# dataloggerver2_0.net
KiCad netlist of a schematic drawn in EAGLE
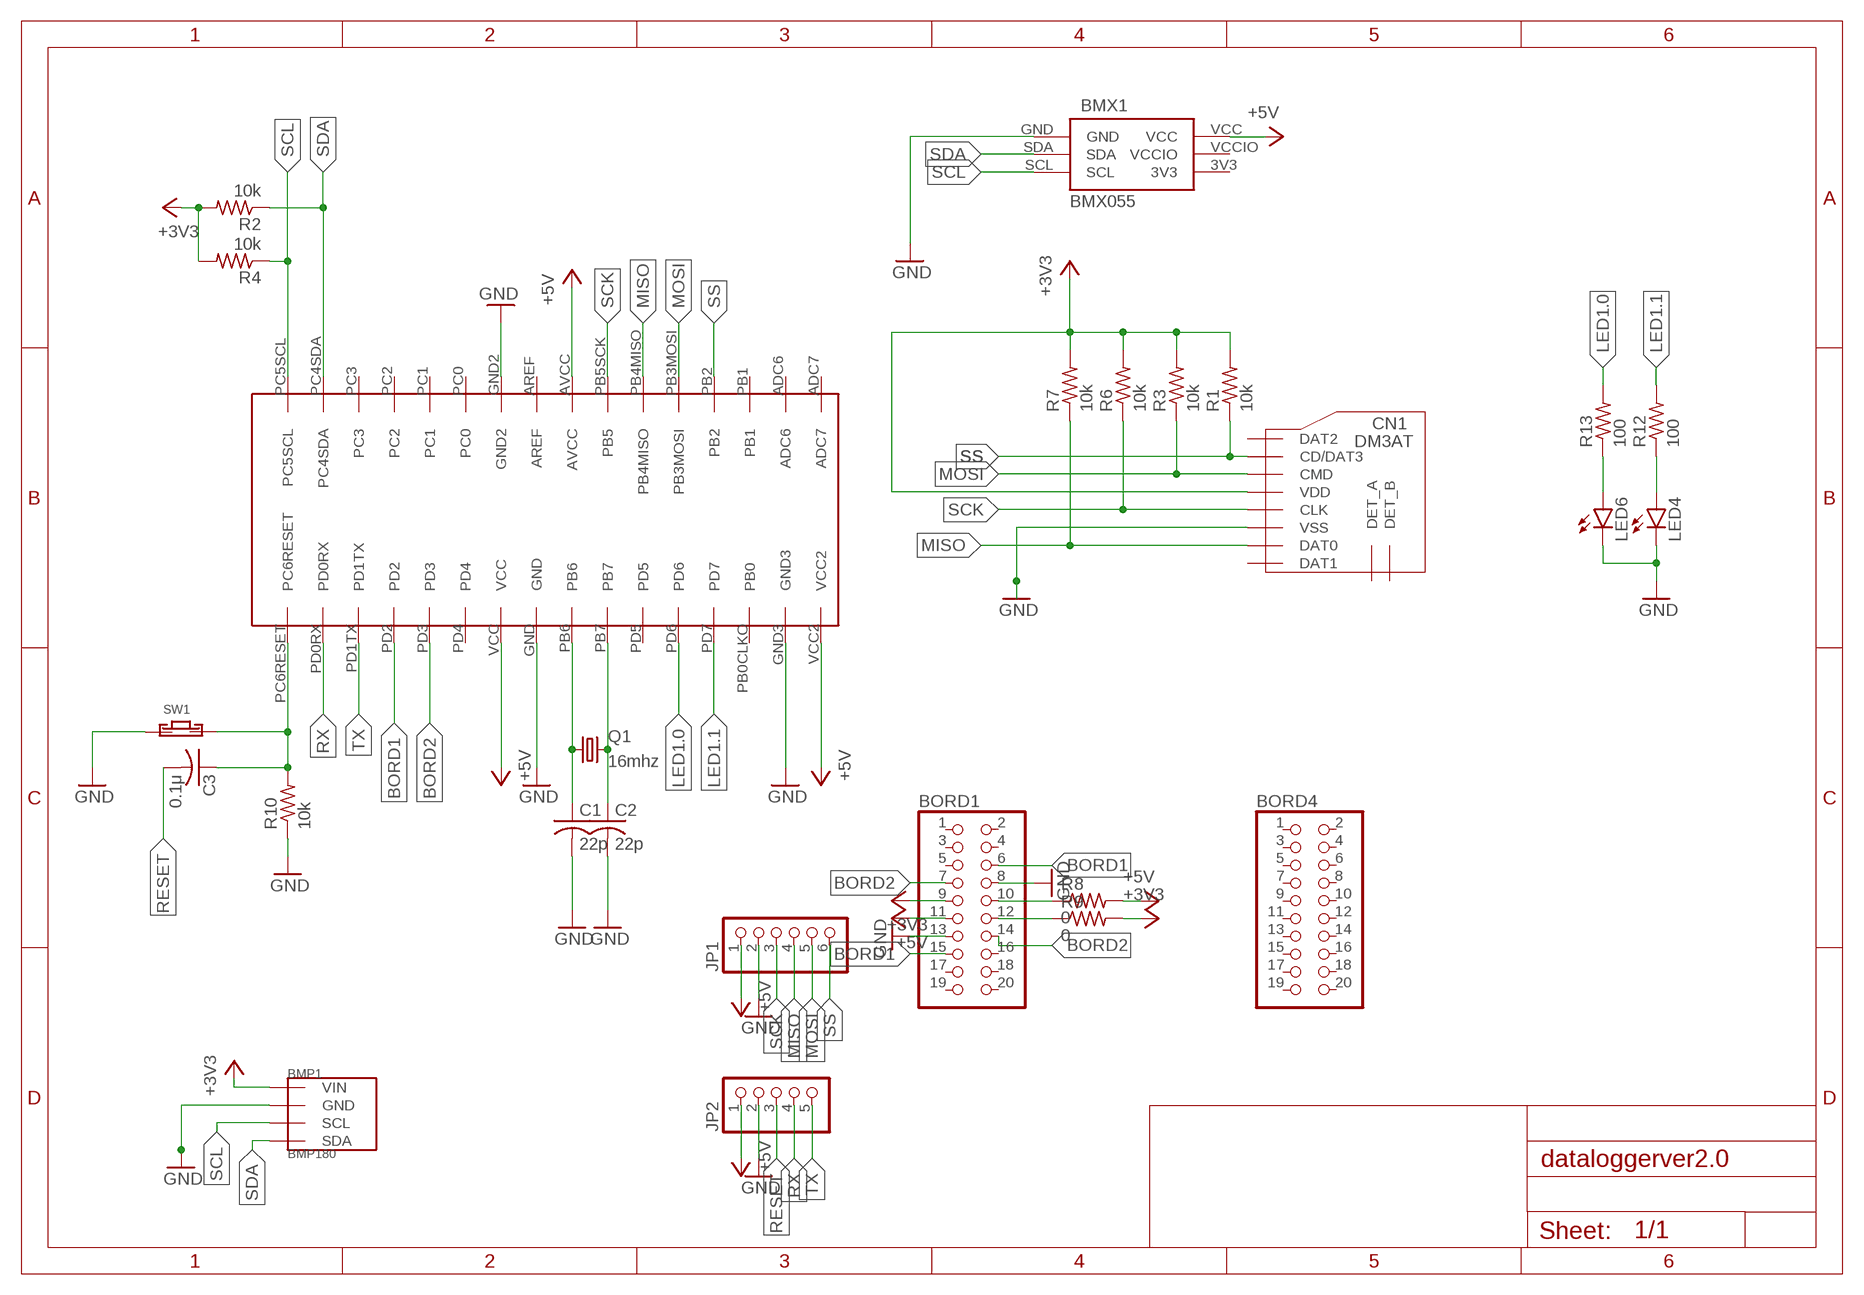
[diagram p0: schematic, sheet 1]

(export (version "E")
  (design (tool "Eeschema 10.0.6"))
  (components
    (comp (ref "BMP1")
      (value "BMP180")
      (footprint "eagle-import:GY-68")
      (libsource (lib "eagle-import") (part "BMP180"))
    )
    (comp (ref "BMX1")
      (value "BMX055")
      (footprint "eagle-import:BMX055")
      (libsource (lib "eagle-import") (part "BMX055"))
    )
    (comp (ref "BORD1")
      (value "PINHD-2X10/90")
      (footprint "eagle-import:2X10_90")
      (libsource (lib "eagle-import") (part "PINHD-2X10/90"))
    )
    (comp (ref "BORD4")
      (value "PINHD-2X10/90")
      (footprint "eagle-import:2X10_90")
      (libsource (lib "eagle-import") (part "PINHD-2X10/90"))
    )
    (comp (ref "C1")
      (value "22p")
      (footprint "eagle-import:C1608")
      (libsource (lib "eagle-import") (part "C-USC1608"))
    )
    (comp (ref "C2")
      (value "22p")
      (footprint "eagle-import:C1608")
      (libsource (lib "eagle-import") (part "C-USC1608"))
    )
    (comp (ref "C3")
      (value "0.1μ")
      (footprint "eagle-import:C1608")
      (libsource (lib "eagle-import") (part "C-USC1608"))
    )
    (comp (ref "CN1")
      (value "DM3AT")
      (footprint "eagle-import:DM3AT")
      (libsource (lib "eagle-import") (part "DM3AT"))
    )
    (comp (ref "JP1")
      (value "PINHD-1X6")
      (footprint "eagle-import:1X06")
      (libsource (lib "eagle-import") (part "PINHD-1X6"))
    )
    (comp (ref "JP2")
      (value "PINHD-1X5")
      (footprint "eagle-import:1X05")
      (libsource (lib "eagle-import") (part "PINHD-1X5"))
    )
    (comp (ref "LED4")
      (value "LED5MM")
      (footprint "eagle-import:LED5MM")
      (libsource (lib "eagle-import") (part "LED5MM"))
    )
    (comp (ref "LED6")
      (value "LED5MM")
      (footprint "eagle-import:LED5MM")
      (libsource (lib "eagle-import") (part "LED5MM"))
    )
    (comp (ref "Q1")
      (value "16mhz")
      (footprint "eagle-import:HC49UP")
      (libsource (lib "eagle-import") (part "CRYSTALHC49UP"))
    )
    (comp (ref "R1")
      (value "10k")
      (footprint "eagle-import:R0603")
      (libsource (lib "eagle-import") (part "R-US_R0603"))
    )
    (comp (ref "R2")
      (value "10k")
      (footprint "eagle-import:R0603")
      (libsource (lib "eagle-import") (part "R-US_R0603"))
    )
    (comp (ref "R3")
      (value "10k")
      (footprint "eagle-import:R0603")
      (libsource (lib "eagle-import") (part "R-US_R0603"))
    )
    (comp (ref "R4")
      (value "10k")
      (footprint "eagle-import:R0603")
      (libsource (lib "eagle-import") (part "R-US_R0603"))
    )
    (comp (ref "R6")
      (value "10k")
      (footprint "eagle-import:R0603")
      (libsource (lib "eagle-import") (part "R-US_R0603"))
    )
    (comp (ref "R7")
      (value "10k")
      (footprint "eagle-import:R0603")
      (libsource (lib "eagle-import") (part "R-US_R0603"))
    )
    (comp (ref "R8")
      (value "0")
      (footprint "eagle-import:R0603")
      (libsource (lib "eagle-import") (part "R-US_R0603"))
    )
    (comp (ref "R9")
      (value "0")
      (footprint "eagle-import:R0603")
      (libsource (lib "eagle-import") (part "R-US_R0603"))
    )
    (comp (ref "R10")
      (value "10k")
      (footprint "eagle-import:R0603")
      (libsource (lib "eagle-import") (part "R-US_R0603"))
    )
    (comp (ref "R12")
      (value "100")
      (footprint "eagle-import:R0603")
      (libsource (lib "eagle-import") (part "R-US_R0603"))
    )
    (comp (ref "R13")
      (value "100")
      (footprint "eagle-import:R0603")
      (libsource (lib "eagle-import") (part "R-US_R0603"))
    )
    (comp (ref "SW1")
      (value "TVAF06-A020B-R")
      (footprint "eagle-import:TVAF06-A020B-R")
      (libsource (lib "eagle-import") (part "TVAF06-A020B-R"))
    )
    (comp (ref "U$1")
      (value "ATMEGA328P-AU")
      (footprint "eagle-import:ATMEGA328P-AU")
      (libsource (lib "eagle-import") (part "ATMEGA328P-AU"))
    )
  )
  (nets
    (net (code "1") (name "+3V3") (class "Default")
      (node (ref "BMP1") (pin "P1") (pinfunction "VIN_P1") (pintype "bidirectional"))
      (node (ref "BORD1") (pin "9") (pinfunction "9_9") (pintype "passive"))
      (node (ref "CN1") (pin "VDD") (pinfunction "VDD_VDD") (pintype "bidirectional"))
      (node (ref "R1") (pin "2") (pinfunction "2_2") (pintype "passive"))
      (node (ref "R2") (pin "2") (pinfunction "2_2") (pintype "passive"))
      (node (ref "R3") (pin "2") (pinfunction "2_2") (pintype "passive"))
      (node (ref "R4") (pin "2") (pinfunction "2_2") (pintype "passive"))
      (node (ref "R6") (pin "2") (pinfunction "2_2") (pintype "passive"))
      (node (ref "R7") (pin "2") (pinfunction "2_2") (pintype "passive"))
      (node (ref "R9") (pin "2") (pinfunction "2_2") (pintype "passive"))
    )
    (net (code "2") (name "+5V") (class "Default")
      (node (ref "BMX1") (pin "VCC") (pinfunction "VCC_VCC") (pintype "power_in"))
      (node (ref "BORD1") (pin "11") (pinfunction "11_11") (pintype "passive"))
      (node (ref "JP1") (pin "1") (pinfunction "1_1") (pintype "passive"))
      (node (ref "JP2") (pin "1") (pinfunction "1_1") (pintype "passive"))
      (node (ref "R8") (pin "2") (pinfunction "2_2") (pintype "passive"))
      (node (ref "U$1") (pin "AVCC") (pinfunction "AVCC_AVCC") (pintype "bidirectional"))
      (node (ref "U$1") (pin "VCC") (pinfunction "VCC_VCC") (pintype "bidirectional"))
      (node (ref "U$1") (pin "VCC2") (pinfunction "VCC2_VCC2") (pintype "bidirectional"))
    )
    (net (code "3") (name "/3V3") (class "Default")
      (node (ref "BMX1") (pin "3V3") (pinfunction "3V3_3V3") (pintype "power_in"))
    )
    (net (code "4") (name "/VCCIO") (class "Default")
      (node (ref "BMX1") (pin "VCCIO") (pinfunction "VCCIO_VCCIO") (pintype "power_in"))
    )
    (net (code "5") (name "BORD1") (class "Default")
      (node (ref "BORD1") (pin "15") (pinfunction "15_15") (pintype "passive"))
      (node (ref "BORD1") (pin "6") (pinfunction "6_6") (pintype "passive"))
      (node (ref "U$1") (pin "PD2") (pinfunction "PD2_PD2") (pintype "bidirectional"))
    )
    (net (code "6") (name "BORD2") (class "Default")
      (node (ref "BORD1") (pin "14") (pinfunction "14_14") (pintype "passive"))
      (node (ref "BORD1") (pin "7") (pinfunction "7_7") (pintype "passive"))
      (node (ref "U$1") (pin "PD3") (pinfunction "PD3_PD3") (pintype "bidirectional"))
    )
    (net (code "7") (name "GND") (class "Default")
      (node (ref "BMP1") (pin "P2") (pinfunction "GND_P2") (pintype "bidirectional"))
      (node (ref "BMX1") (pin "GND") (pinfunction "GND_GND") (pintype "power_in"))
      (node (ref "BORD1") (pin "13") (pinfunction "13_13") (pintype "passive"))
      (node (ref "BORD1") (pin "8") (pinfunction "8_8") (pintype "passive"))
      (node (ref "C1") (pin "2") (pinfunction "2_2") (pintype "passive"))
      (node (ref "C2") (pin "2") (pinfunction "2_2") (pintype "passive"))
      (node (ref "CN1") (pin "VSS") (pinfunction "VSS_VSS") (pintype "bidirectional"))
      (node (ref "JP1") (pin "2") (pinfunction "2_2") (pintype "passive"))
      (node (ref "JP2") (pin "2") (pinfunction "2_2") (pintype "passive"))
      (node (ref "LED4") (pin "K") (pinfunction "C_K") (pintype "passive"))
      (node (ref "LED6") (pin "K") (pinfunction "C_K") (pintype "passive"))
      (node (ref "R10") (pin "1") (pinfunction "1_1") (pintype "passive"))
      (node (ref "SW1") (pin "P$1") (pinfunction "P$1_P$1") (pintype "bidirectional"))
      (node (ref "U$1") (pin "GND") (pinfunction "GND_GND") (pintype "bidirectional"))
      (node (ref "U$1") (pin "GND2") (pinfunction "GND2_GND2") (pintype "bidirectional"))
      (node (ref "U$1") (pin "GND3") (pinfunction "GND3_GND3") (pintype "bidirectional"))
    )
    (net (code "8") (name "LED1.0") (class "Default")
      (node (ref "R13") (pin "2") (pinfunction "2_2") (pintype "passive"))
      (node (ref "U$1") (pin "PD6") (pinfunction "PD6_PD6") (pintype "bidirectional"))
    )
    (net (code "9") (name "LED1.1") (class "Default")
      (node (ref "R12") (pin "2") (pinfunction "2_2") (pintype "passive"))
      (node (ref "U$1") (pin "PD7") (pinfunction "PD7_PD7") (pintype "bidirectional"))
    )
    (net (code "10") (name "MISO") (class "Default")
      (node (ref "CN1") (pin "DAT0") (pinfunction "DAT0_DAT0") (pintype "bidirectional"))
      (node (ref "JP1") (pin "4") (pinfunction "4_4") (pintype "passive"))
      (node (ref "R7") (pin "1") (pinfunction "1_1") (pintype "passive"))
      (node (ref "U$1") (pin "PB4MISO") (pinfunction "PB4MISO_PB4MISO") (pintype "bidirectional"))
    )
    (net (code "11") (name "MOSI") (class "Default")
      (node (ref "CN1") (pin "CMD") (pinfunction "CMD_CMD") (pintype "bidirectional"))
      (node (ref "JP1") (pin "5") (pinfunction "5_5") (pintype "passive"))
      (node (ref "R3") (pin "1") (pinfunction "1_1") (pintype "passive"))
      (node (ref "U$1") (pin "PB3MOSI") (pinfunction "PB3MOSI_PB3MOSI") (pintype "bidirectional"))
    )
    (net (code "12") (name "Net-(BORD1-Pad10)") (class "Default")
      (node (ref "BORD1") (pin "10") (pinfunction "10_10") (pintype "passive"))
      (node (ref "R8") (pin "1") (pinfunction "1_1") (pintype "passive"))
    )
    (net (code "13") (name "Net-(BORD1-Pad12)") (class "Default")
      (node (ref "BORD1") (pin "12") (pinfunction "12_12") (pintype "passive"))
      (node (ref "R9") (pin "1") (pinfunction "1_1") (pintype "passive"))
    )
    (net (code "14") (name "Net-(C1-Pad1)") (class "Default")
      (node (ref "C1") (pin "1") (pinfunction "1_1") (pintype "passive"))
      (node (ref "Q1") (pin "1") (pinfunction "1_1") (pintype "passive"))
      (node (ref "U$1") (pin "PB6") (pinfunction "PB6_PB6") (pintype "bidirectional"))
    )
    (net (code "15") (name "Net-(C2-Pad1)") (class "Default")
      (node (ref "C2") (pin "1") (pinfunction "1_1") (pintype "passive"))
      (node (ref "Q1") (pin "2") (pinfunction "2_2") (pintype "passive"))
      (node (ref "U$1") (pin "PB7") (pinfunction "PB7_PB7") (pintype "bidirectional"))
    )
    (net (code "16") (name "Net-(C3-Pad1)") (class "Default")
      (node (ref "C3") (pin "1") (pinfunction "1_1") (pintype "passive"))
      (node (ref "R10") (pin "2") (pinfunction "2_2") (pintype "passive"))
      (node (ref "SW1") (pin "P$2") (pinfunction "P$2_P$2") (pintype "bidirectional"))
      (node (ref "U$1") (pin "PC6RESET") (pinfunction "PC6RESET_PC6RESET") (pintype "bidirectional"))
    )
    (net (code "17") (name "Net-(LED4-PadA)") (class "Default")
      (node (ref "LED4") (pin "A") (pinfunction "A_A") (pintype "passive"))
      (node (ref "R12") (pin "1") (pinfunction "1_1") (pintype "passive"))
    )
    (net (code "18") (name "Net-(LED6-PadA)") (class "Default")
      (node (ref "LED6") (pin "A") (pinfunction "A_A") (pintype "passive"))
      (node (ref "R13") (pin "1") (pinfunction "1_1") (pintype "passive"))
    )
    (net (code "19") (name "RESET") (class "Default")
      (node (ref "C3") (pin "2") (pinfunction "2_2") (pintype "passive"))
      (node (ref "JP2") (pin "3") (pinfunction "3_3") (pintype "passive"))
    )
    (net (code "20") (name "RX") (class "Default")
      (node (ref "JP2") (pin "4") (pinfunction "4_4") (pintype "passive"))
      (node (ref "U$1") (pin "PD0RX") (pinfunction "PD0RX_PD0RX") (pintype "bidirectional"))
    )
    (net (code "21") (name "SCK") (class "Default")
      (node (ref "CN1") (pin "CLK") (pinfunction "CLK_CLK") (pintype "bidirectional"))
      (node (ref "JP1") (pin "3") (pinfunction "3_3") (pintype "passive"))
      (node (ref "R6") (pin "1") (pinfunction "1_1") (pintype "passive"))
      (node (ref "U$1") (pin "PB5SCK") (pinfunction "PB5_PB5SCK") (pintype "bidirectional"))
    )
    (net (code "22") (name "SCL") (class "Default")
      (node (ref "BMP1") (pin "P3") (pinfunction "SCL_P3") (pintype "bidirectional"))
      (node (ref "BMX1") (pin "SCL") (pinfunction "SCL_SCL") (pintype "bidirectional"))
      (node (ref "R4") (pin "1") (pinfunction "1_1") (pintype "passive"))
      (node (ref "U$1") (pin "PC5SCL") (pinfunction "PC5SCL_PC5SCL") (pintype "bidirectional"))
    )
    (net (code "23") (name "SDA") (class "Default")
      (node (ref "BMP1") (pin "P4") (pinfunction "SDA_P4") (pintype "bidirectional"))
      (node (ref "BMX1") (pin "SDA") (pinfunction "SDA_SDA") (pintype "bidirectional"))
      (node (ref "R2") (pin "1") (pinfunction "1_1") (pintype "passive"))
      (node (ref "U$1") (pin "PC4SDA") (pinfunction "PC4SDA_PC4SDA") (pintype "bidirectional"))
    )
    (net (code "24") (name "SS") (class "Default")
      (node (ref "CN1") (pin "CD/DAT3") (pinfunction "CD/DAT3_CD/DAT3") (pintype "bidirectional"))
      (node (ref "JP1") (pin "6") (pinfunction "6_6") (pintype "passive"))
      (node (ref "R1") (pin "1") (pinfunction "1_1") (pintype "passive"))
      (node (ref "U$1") (pin "PB2") (pinfunction "PB2_PB2") (pintype "bidirectional"))
    )
    (net (code "25") (name "TX") (class "Default")
      (node (ref "JP2") (pin "5") (pinfunction "5_5") (pintype "passive"))
      (node (ref "U$1") (pin "PD1TX") (pinfunction "PD1TX_PD1TX") (pintype "bidirectional"))
    )
    (net (code "26") (name "unconnected-(BORD1-Pad1)") (class "Default")
      (node (ref "BORD1") (pin "1") (pinfunction "1_1") (pintype "passive"))
    )
    (net (code "27") (name "unconnected-(BORD1-Pad2)") (class "Default")
      (node (ref "BORD1") (pin "2") (pinfunction "2_2") (pintype "passive"))
    )
    (net (code "28") (name "unconnected-(BORD1-Pad3)") (class "Default")
      (node (ref "BORD1") (pin "3") (pinfunction "3_3") (pintype "passive"))
    )
    (net (code "29") (name "unconnected-(BORD1-Pad4)") (class "Default")
      (node (ref "BORD1") (pin "4") (pinfunction "4_4") (pintype "passive"))
    )
    (net (code "30") (name "unconnected-(BORD1-Pad5)") (class "Default")
      (node (ref "BORD1") (pin "5") (pinfunction "5_5") (pintype "passive"))
    )
    (net (code "31") (name "unconnected-(BORD1-Pad16)") (class "Default")
      (node (ref "BORD1") (pin "16") (pinfunction "16_16") (pintype "passive"))
    )
    (net (code "32") (name "unconnected-(BORD1-Pad17)") (class "Default")
      (node (ref "BORD1") (pin "17") (pinfunction "17_17") (pintype "passive"))
    )
    (net (code "33") (name "unconnected-(BORD1-Pad18)") (class "Default")
      (node (ref "BORD1") (pin "18") (pinfunction "18_18") (pintype "passive"))
    )
    (net (code "34") (name "unconnected-(BORD1-Pad19)") (class "Default")
      (node (ref "BORD1") (pin "19") (pinfunction "19_19") (pintype "passive"))
    )
    (net (code "35") (name "unconnected-(BORD1-Pad20)") (class "Default")
      (node (ref "BORD1") (pin "20") (pinfunction "20_20") (pintype "passive"))
    )
    (net (code "36") (name "unconnected-(BORD4-Pad1)") (class "Default")
      (node (ref "BORD4") (pin "1") (pinfunction "1_1") (pintype "passive"))
    )
    (net (code "37") (name "unconnected-(BORD4-Pad2)") (class "Default")
      (node (ref "BORD4") (pin "2") (pinfunction "2_2") (pintype "passive"))
    )
    (net (code "38") (name "unconnected-(BORD4-Pad3)") (class "Default")
      (node (ref "BORD4") (pin "3") (pinfunction "3_3") (pintype "passive"))
    )
    (net (code "39") (name "unconnected-(BORD4-Pad4)") (class "Default")
      (node (ref "BORD4") (pin "4") (pinfunction "4_4") (pintype "passive"))
    )
    (net (code "40") (name "unconnected-(BORD4-Pad5)") (class "Default")
      (node (ref "BORD4") (pin "5") (pinfunction "5_5") (pintype "passive"))
    )
    (net (code "41") (name "unconnected-(BORD4-Pad6)") (class "Default")
      (node (ref "BORD4") (pin "6") (pinfunction "6_6") (pintype "passive"))
    )
    (net (code "42") (name "unconnected-(BORD4-Pad7)") (class "Default")
      (node (ref "BORD4") (pin "7") (pinfunction "7_7") (pintype "passive"))
    )
    (net (code "43") (name "unconnected-(BORD4-Pad8)") (class "Default")
      (node (ref "BORD4") (pin "8") (pinfunction "8_8") (pintype "passive"))
    )
    (net (code "44") (name "unconnected-(BORD4-Pad9)") (class "Default")
      (node (ref "BORD4") (pin "9") (pinfunction "9_9") (pintype "passive"))
    )
    (net (code "45") (name "unconnected-(BORD4-Pad10)") (class "Default")
      (node (ref "BORD4") (pin "10") (pinfunction "10_10") (pintype "passive"))
    )
    (net (code "46") (name "unconnected-(BORD4-Pad11)") (class "Default")
      (node (ref "BORD4") (pin "11") (pinfunction "11_11") (pintype "passive"))
    )
    (net (code "47") (name "unconnected-(BORD4-Pad12)") (class "Default")
      (node (ref "BORD4") (pin "12") (pinfunction "12_12") (pintype "passive"))
    )
    (net (code "48") (name "unconnected-(BORD4-Pad13)") (class "Default")
      (node (ref "BORD4") (pin "13") (pinfunction "13_13") (pintype "passive"))
    )
    (net (code "49") (name "unconnected-(BORD4-Pad14)") (class "Default")
      (node (ref "BORD4") (pin "14") (pinfunction "14_14") (pintype "passive"))
    )
    (net (code "50") (name "unconnected-(BORD4-Pad15)") (class "Default")
      (node (ref "BORD4") (pin "15") (pinfunction "15_15") (pintype "passive"))
    )
    (net (code "51") (name "unconnected-(BORD4-Pad16)") (class "Default")
      (node (ref "BORD4") (pin "16") (pinfunction "16_16") (pintype "passive"))
    )
    (net (code "52") (name "unconnected-(BORD4-Pad17)") (class "Default")
      (node (ref "BORD4") (pin "17") (pinfunction "17_17") (pintype "passive"))
    )
    (net (code "53") (name "unconnected-(BORD4-Pad18)") (class "Default")
      (node (ref "BORD4") (pin "18") (pinfunction "18_18") (pintype "passive"))
    )
    (net (code "54") (name "unconnected-(BORD4-Pad19)") (class "Default")
      (node (ref "BORD4") (pin "19") (pinfunction "19_19") (pintype "passive"))
    )
    (net (code "55") (name "unconnected-(BORD4-Pad20)") (class "Default")
      (node (ref "BORD4") (pin "20") (pinfunction "20_20") (pintype "passive"))
    )
    (net (code "56") (name "unconnected-(CN1-PadDAT1)") (class "Default")
      (node (ref "CN1") (pin "DAT1") (pinfunction "DAT1_DAT1") (pintype "bidirectional"))
    )
    (net (code "57") (name "unconnected-(CN1-PadDAT2)") (class "Default")
      (node (ref "CN1") (pin "DAT2") (pinfunction "DAT2_DAT2") (pintype "bidirectional"))
    )
    (net (code "58") (name "unconnected-(CN1-PadDET_A)") (class "Default")
      (node (ref "CN1") (pin "DET_A") (pinfunction "DET_A_DET_A") (pintype "bidirectional"))
    )
    (net (code "59") (name "unconnected-(CN1-PadDET_B)") (class "Default")
      (node (ref "CN1") (pin "DET_B") (pinfunction "DET_B_DET_B") (pintype "bidirectional"))
    )
    (net (code "60") (name "unconnected-(U$1-PB0-PadPB0CLKO)") (class "Default")
      (node (ref "U$1") (pin "PB0CLKO") (pinfunction "PB0_PB0CLKO") (pintype "bidirectional"))
    )
    (net (code "61") (name "unconnected-(U$1-PadADC6)") (class "Default")
      (node (ref "U$1") (pin "ADC6") (pinfunction "ADC6_ADC6") (pintype "bidirectional"))
    )
    (net (code "62") (name "unconnected-(U$1-PadADC7)") (class "Default")
      (node (ref "U$1") (pin "ADC7") (pinfunction "ADC7_ADC7") (pintype "bidirectional"))
    )
    (net (code "63") (name "unconnected-(U$1-PadAREF)") (class "Default")
      (node (ref "U$1") (pin "AREF") (pinfunction "AREF_AREF") (pintype "bidirectional"))
    )
    (net (code "64") (name "unconnected-(U$1-PadPB1)") (class "Default")
      (node (ref "U$1") (pin "PB1") (pinfunction "PB1_PB1") (pintype "bidirectional"))
    )
    (net (code "65") (name "unconnected-(U$1-PadPC0)") (class "Default")
      (node (ref "U$1") (pin "PC0") (pinfunction "PC0_PC0") (pintype "bidirectional"))
    )
    (net (code "66") (name "unconnected-(U$1-PadPC1)") (class "Default")
      (node (ref "U$1") (pin "PC1") (pinfunction "PC1_PC1") (pintype "bidirectional"))
    )
    (net (code "67") (name "unconnected-(U$1-PadPC2)") (class "Default")
      (node (ref "U$1") (pin "PC2") (pinfunction "PC2_PC2") (pintype "bidirectional"))
    )
    (net (code "68") (name "unconnected-(U$1-PadPC3)") (class "Default")
      (node (ref "U$1") (pin "PC3") (pinfunction "PC3_PC3") (pintype "bidirectional"))
    )
    (net (code "69") (name "unconnected-(U$1-PadPD4)") (class "Default")
      (node (ref "U$1") (pin "PD4") (pinfunction "PD4_PD4") (pintype "bidirectional"))
    )
    (net (code "70") (name "unconnected-(U$1-PadPD5)") (class "Default")
      (node (ref "U$1") (pin "PD5") (pinfunction "PD5_PD5") (pintype "bidirectional"))
    )
  )
)
